# 1_Triangle_Wave_Generator.net
KiCad netlist of a schematic drawn in Altium Designer
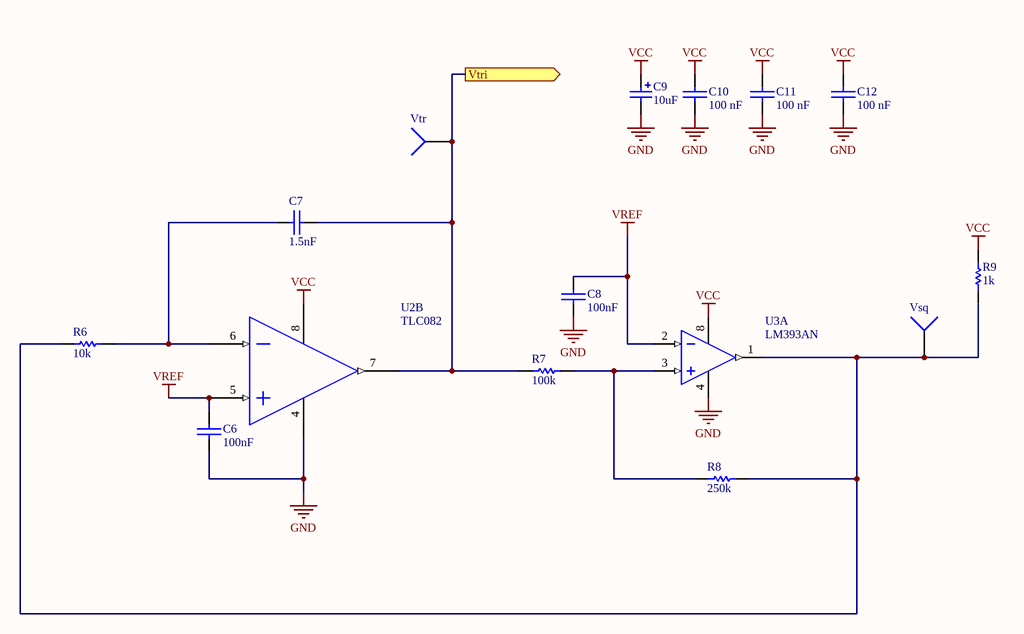
[diagram p0: 1_Triangle Wave Generator.SchDoc]

(export (version "E")
  (design (tool "Eeschema 10.0.6"))
  (components
    (comp (ref "C6")
      (value "100nF")
      (footprint "ece-RAD0.2")
      (description "Capacitor Non Polarised Through Hole")
      (libsource (lib "ece components") (part "CAP"))
    )
    (comp (ref "C7")
      (value "1.5nF")
      (footprint "ece-RAD0.2")
      (description "Capacitor Non Polarised Through Hole")
      (libsource (lib "ece components") (part "CAP"))
    )
    (comp (ref "C8")
      (value "100nF")
      (footprint "ece-RAD0.2")
      (description "Capacitor Non Polarised Through Hole")
      (libsource (lib "ece components") (part "CAP"))
    )
    (comp (ref "C9")
      (value "10uF")
      (footprint "ece-CAPAD2TH0.3")
      (description "Polarized Capacitor (Radial)")
      (fields (field (name "MANUFACTURER") "Generic Components") (field (name "PUBLISHER") "Altium Limited"))
      (libsource (lib "ece components") (part "CAP 22uF TH"))
    )
    (comp (ref "C10")
      (value "100 nF")
      (footprint "ece-RAD0.2")
      (description "Capacitor Non Polarised Through Hole")
      (libsource (lib "ece components") (part "CAP"))
    )
    (comp (ref "C11")
      (value "100 nF")
      (footprint "ece-RAD0.2")
      (description "Capacitor Non Polarised Through Hole")
      (libsource (lib "ece components") (part "CAP"))
    )
    (comp (ref "C12")
      (value "100 nF")
      (footprint "ece-RAD0.2")
      (description "Capacitor Non Polarised Through Hole")
      (libsource (lib "ece components") (part "CAP"))
    )
    (comp (ref "R6")
      (value "10k")
      (footprint "ece-AXIAL0.4")
      (description "Resistor")
      (fields (field (name "PUBLISHER") "Altium Limited"))
      (libsource (lib "ece components") (part "Res1"))
    )
    (comp (ref "R7")
      (value "100k")
      (footprint "ece-AXIAL0.4")
      (description "Resistor")
      (fields (field (name "PUBLISHER") "Altium Limited"))
      (libsource (lib "ece components") (part "Res1"))
    )
    (comp (ref "R8")
      (value "250k")
      (footprint "ece-AXIAL0.4")
      (description "Resistor")
      (fields (field (name "PUBLISHER") "Altium Limited"))
      (libsource (lib "ece components") (part "Res1"))
    )
    (comp (ref "R9")
      (value "1k")
      (footprint "ece-AXIAL0.4")
      (description "Resistor")
      (fields (field (name "PUBLISHER") "Altium Limited"))
      (libsource (lib "ece components") (part "Res1"))
    )
    (comp (ref "U2")
      (value "TLC082")
      (footprint "ECE-DIP8")
      (libsource (lib "ece components") (part "TLC082"))
    )
    (comp (ref "U3")
      (value "LM393AN")
      (footprint "ECE-DIP8")
      (description "Dual Comparator")
      (fields (field (name "PUBLISHER") "Altium Limited"))
      (libsource (lib "ece components") (part "LM393AN"))
    )
    (comp (ref "Vsq")
      (value "GND")
      (footprint "ece-HDR1")
      (description "Socket")
      (fields (field (name "PUBLISHER") "Altium Limited"))
      (libsource (lib "ece components") (part "Test pin"))
    )
    (comp (ref "Vtr")
      (value "GND")
      (footprint "ece-HDR1")
      (description "Socket")
      (fields (field (name "PUBLISHER") "Altium Limited"))
      (libsource (lib "ece components") (part "Test pin"))
    )
  )
  (nets
    (net (code "1") (name "/Vtri") (class "Default")
      (node (ref "C7") (pin "2") (pinfunction "2_2") (pintype "passive"))
      (node (ref "R7") (pin "1") (pinfunction "1_1") (pintype "passive"))
      (node (ref "U2") (pin "7") (pinfunction "OUT2_7") (pintype "output"))
      (node (ref "Vtr") (pin "1") (pinfunction "1_1") (pintype "passive"))
    )
    (net (code "2") (name "GND") (class "Default")
      (node (ref "C10") (pin "2") (pinfunction "2_2") (pintype "passive"))
      (node (ref "C11") (pin "2") (pinfunction "2_2") (pintype "passive"))
      (node (ref "C12") (pin "2") (pinfunction "2_2") (pintype "passive"))
      (node (ref "C6") (pin "1") (pinfunction "1_1") (pintype "passive"))
      (node (ref "C8") (pin "1") (pinfunction "1_1") (pintype "passive"))
      (node (ref "C9") (pin "2") (pinfunction "2_2") (pintype "passive"))
      (node (ref "U2") (pin "4") (pinfunction "GND_4") (pintype "power_in"))
      (node (ref "U3") (pin "4") (pinfunction "GND_4") (pintype "power_in"))
    )
    (net (code "3") (name "Net-(U2B-IN2(-))") (class "Default")
      (node (ref "C7") (pin "1") (pinfunction "1_1") (pintype "passive"))
      (node (ref "R6") (pin "2") (pinfunction "2_2") (pintype "passive"))
      (node (ref "U2") (pin "6") (pinfunction "IN2(-)_6") (pintype "input"))
    )
    (net (code "4") (name "Net-(U3A-IN+)") (class "Default")
      (node (ref "R7") (pin "2") (pinfunction "2_2") (pintype "passive"))
      (node (ref "R8") (pin "1") (pinfunction "1_1") (pintype "passive"))
      (node (ref "U3") (pin "3") (pinfunction "IN+_3") (pintype "input"))
    )
    (net (code "5") (name "Net-(U3A-OUT)") (class "Default")
      (node (ref "R6") (pin "1") (pinfunction "1_1") (pintype "passive"))
      (node (ref "R8") (pin "2") (pinfunction "2_2") (pintype "passive"))
      (node (ref "R9") (pin "1") (pinfunction "1_1") (pintype "passive"))
      (node (ref "U3") (pin "1") (pinfunction "OUT_1") (pintype "output"))
      (node (ref "Vsq") (pin "1") (pinfunction "1_1") (pintype "passive"))
    )
    (net (code "6") (name "VCC") (class "Default")
      (node (ref "C10") (pin "1") (pinfunction "1_1") (pintype "passive"))
      (node (ref "C11") (pin "1") (pinfunction "1_1") (pintype "passive"))
      (node (ref "C12") (pin "1") (pinfunction "1_1") (pintype "passive"))
      (node (ref "C9") (pin "1") (pinfunction "1_1") (pintype "passive"))
      (node (ref "R9") (pin "2") (pinfunction "2_2") (pintype "passive"))
      (node (ref "U2") (pin "8") (pinfunction "V(+)_8") (pintype "power_in"))
      (node (ref "U3") (pin "8") (pinfunction "V+_8") (pintype "power_in"))
    )
    (net (code "7") (name "VREF") (class "Default")
      (node (ref "C6") (pin "2") (pinfunction "2_2") (pintype "passive"))
      (node (ref "C8") (pin "2") (pinfunction "2_2") (pintype "passive"))
      (node (ref "U2") (pin "5") (pinfunction "IN2(+)_5") (pintype "input"))
      (node (ref "U3") (pin "2") (pinfunction "IN-_2") (pintype "input"))
    )
  )
)
